# atmega328_core.net
KiCad netlist of a schematic drawn in EAGLE
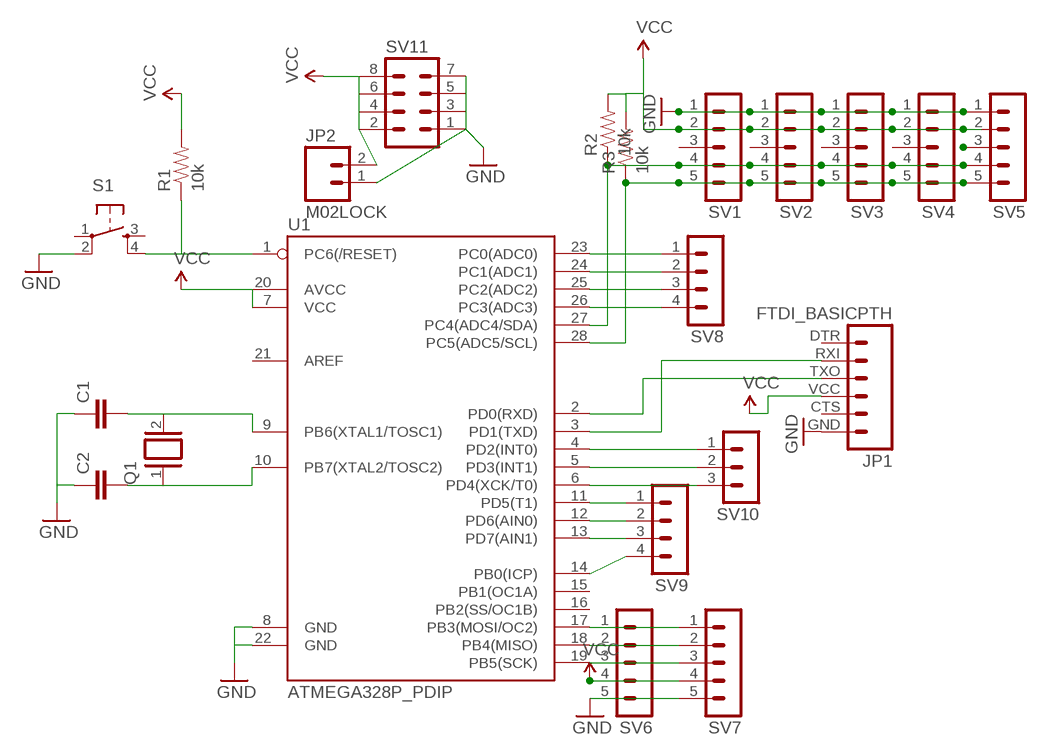
[diagram p0: schematic, sheet 1]

(export (version "E")
  (design (tool "Eeschema 10.0.6"))
  (components
    (comp (ref "C1")
      (value "CAPEZ")
      (footprint "eagle-import:CAP-PTH-SMALLEZ")
      (libsource (lib "eagle-import") (part "CAPEZ"))
    )
    (comp (ref "C2")
      (value "CAPEZ")
      (footprint "eagle-import:CAP-PTH-SMALLEZ")
      (libsource (lib "eagle-import") (part "CAPEZ"))
    )
    (comp (ref "JP1")
      (value "FTDI_BASICPTH")
      (footprint "eagle-import:FTDI_BASIC")
      (libsource (lib "eagle-import") (part "FTDI_BASICPTH"))
    )
    (comp (ref "JP2")
      (value "M02LOCK")
      (footprint "eagle-import:1X02_LOCK")
      (libsource (lib "eagle-import") (part "M02LOCK"))
    )
    (comp (ref "Q1")
      (value "XTAL/S")
      (footprint "eagle-import:QS")
      (libsource (lib "eagle-import") (part "XTAL/S"))
    )
    (comp (ref "R1")
      (value "10k")
      (footprint "eagle-import:AXIAL-0.3-KIT")
      (libsource (lib "eagle-import") (part "RESISTORKIT"))
    )
    (comp (ref "R2")
      (value "10k")
      (footprint "eagle-import:AXIAL-0.3-KIT")
      (libsource (lib "eagle-import") (part "RESISTORKIT"))
    )
    (comp (ref "R3")
      (value "10k")
      (footprint "eagle-import:AXIAL-0.3-KIT")
      (libsource (lib "eagle-import") (part "RESISTORKIT"))
    )
    (comp (ref "S1")
      (value "TAC_SWITCHPTH")
      (footprint "eagle-import:TACTILE-PTH")
      (libsource (lib "eagle-import") (part "TAC_SWITCHPTH"))
    )
    (comp (ref "SV1")
      (value "MA05-1")
      (footprint "eagle-import:MA05-1")
      (libsource (lib "eagle-import") (part "MA05-1"))
    )
    (comp (ref "SV2")
      (value "MA05-1")
      (footprint "eagle-import:MA05-1")
      (libsource (lib "eagle-import") (part "MA05-1"))
    )
    (comp (ref "SV3")
      (value "MA05-1")
      (footprint "eagle-import:MA05-1")
      (libsource (lib "eagle-import") (part "MA05-1"))
    )
    (comp (ref "SV4")
      (value "MA05-1")
      (footprint "eagle-import:MA05-1")
      (libsource (lib "eagle-import") (part "MA05-1"))
    )
    (comp (ref "SV5")
      (value "MA05-1")
      (footprint "eagle-import:MA05-1")
      (libsource (lib "eagle-import") (part "MA05-1"))
    )
    (comp (ref "SV6")
      (value "MA05-1")
      (footprint "eagle-import:MA05-1")
      (libsource (lib "eagle-import") (part "MA05-1"))
    )
    (comp (ref "SV7")
      (value "MA05-1")
      (footprint "eagle-import:MA05-1")
      (libsource (lib "eagle-import") (part "MA05-1"))
    )
    (comp (ref "SV8")
      (value "MA04-1")
      (footprint "eagle-import:MA04-1")
      (libsource (lib "eagle-import") (part "MA04-1"))
    )
    (comp (ref "SV9")
      (value "MA04-1")
      (footprint "eagle-import:MA04-1")
      (libsource (lib "eagle-import") (part "MA04-1"))
    )
    (comp (ref "SV10")
      (value "MA03-1")
      (footprint "eagle-import:MA03-1")
      (libsource (lib "eagle-import") (part "MA03-1"))
    )
    (comp (ref "SV11")
      (value "MA04-2")
      (footprint "eagle-import:MA04-2")
      (libsource (lib "eagle-import") (part "MA04-2"))
    )
    (comp (ref "U1")
      (value "ATMEGA328P_PDIP")
      (footprint "eagle-import:DIL28-3")
      (libsource (lib "eagle-import") (part "ATMEGA328P_PDIP"))
    )
  )
  (nets
    (net (code "1") (name "GND") (class "Default")
      (node (ref "C1") (pin "1") (pinfunction "1_1") (pintype "passive"))
      (node (ref "C2") (pin "1") (pinfunction "1_1") (pintype "passive"))
      (node (ref "JP1") (pin "GND") (pinfunction "6_GND") (pintype "passive"))
      (node (ref "JP2") (pin "1") (pinfunction "1_1") (pintype "passive"))
      (node (ref "S1") (pin "2") (pinfunction "2_2") (pintype "passive"))
      (node (ref "SV1") (pin "1") (pinfunction "1_1") (pintype "passive"))
      (node (ref "SV11") (pin "1") (pinfunction "1_1") (pintype "passive"))
      (node (ref "SV11") (pin "3") (pinfunction "3_3") (pintype "passive"))
      (node (ref "SV11") (pin "5") (pinfunction "5_5") (pintype "passive"))
      (node (ref "SV11") (pin "7") (pinfunction "7_7") (pintype "passive"))
      (node (ref "SV2") (pin "1") (pinfunction "1_1") (pintype "passive"))
      (node (ref "SV3") (pin "1") (pinfunction "1_1") (pintype "passive"))
      (node (ref "SV4") (pin "1") (pinfunction "1_1") (pintype "passive"))
      (node (ref "SV5") (pin "1") (pinfunction "1_1") (pintype "passive"))
      (node (ref "SV6") (pin "5") (pinfunction "5_5") (pintype "passive"))
      (node (ref "SV7") (pin "5") (pinfunction "5_5") (pintype "passive"))
      (node (ref "U1") (pin "22") (pinfunction "GND_22") (pintype "bidirectional"))
      (node (ref "U1") (pin "8") (pinfunction "GND_8") (pintype "bidirectional"))
    )
    (net (code "2") (name "Net-(JP1-2)") (class "Default")
      (node (ref "JP1") (pin "RXI") (pinfunction "2_RXI") (pintype "passive"))
      (node (ref "U1") (pin "3") (pinfunction "PD1(TXD)_3") (pintype "bidirectional"))
    )
    (net (code "3") (name "Net-(JP1-3)") (class "Default")
      (node (ref "JP1") (pin "TXO") (pinfunction "3_TXO") (pintype "passive"))
      (node (ref "U1") (pin "2") (pinfunction "PD0(RXD)_2") (pintype "bidirectional"))
    )
    (net (code "4") (name "Net-(R1-1)") (class "Default")
      (node (ref "R1") (pin "P$1") (pinfunction "1_P$1") (pintype "passive"))
      (node (ref "S1") (pin "4") (pinfunction "4_4") (pintype "passive"))
      (node (ref "U1") (pin "1") (pinfunction "PC6(/RESET)_1") (pintype "bidirectional"))
    )
    (net (code "5") (name "Net-(R2-1)") (class "Default")
      (node (ref "R2") (pin "P$1") (pinfunction "1_P$1") (pintype "passive"))
      (node (ref "SV1") (pin "4") (pinfunction "4_4") (pintype "passive"))
      (node (ref "SV2") (pin "4") (pinfunction "4_4") (pintype "passive"))
      (node (ref "SV3") (pin "4") (pinfunction "4_4") (pintype "passive"))
      (node (ref "SV4") (pin "4") (pinfunction "4_4") (pintype "passive"))
      (node (ref "SV5") (pin "4") (pinfunction "4_4") (pintype "passive"))
      (node (ref "U1") (pin "27") (pinfunction "PC4(ADC4/SDA)_27") (pintype "bidirectional"))
    )
    (net (code "6") (name "Net-(R3-1)") (class "Default")
      (node (ref "R3") (pin "P$1") (pinfunction "1_P$1") (pintype "passive"))
      (node (ref "SV1") (pin "5") (pinfunction "5_5") (pintype "passive"))
      (node (ref "SV2") (pin "5") (pinfunction "5_5") (pintype "passive"))
      (node (ref "SV3") (pin "5") (pinfunction "5_5") (pintype "passive"))
      (node (ref "SV4") (pin "5") (pinfunction "5_5") (pintype "passive"))
      (node (ref "SV5") (pin "5") (pinfunction "5_5") (pintype "passive"))
      (node (ref "U1") (pin "28") (pinfunction "PC5(ADC5/SCL)_28") (pintype "bidirectional"))
    )
    (net (code "7") (name "Net-(U1-PB0(ICP))") (class "Default")
      (node (ref "SV9") (pin "4") (pinfunction "4_4") (pintype "passive"))
      (node (ref "U1") (pin "14") (pinfunction "PB0(ICP)_14") (pintype "bidirectional"))
    )
    (net (code "8") (name "Net-(U1-PB3(MOSI{slash}OC2))") (class "Default")
      (node (ref "SV6") (pin "1") (pinfunction "1_1") (pintype "passive"))
      (node (ref "SV7") (pin "1") (pinfunction "1_1") (pintype "passive"))
      (node (ref "U1") (pin "17") (pinfunction "PB3(MOSI/OC2)_17") (pintype "bidirectional"))
    )
    (net (code "9") (name "Net-(U1-PB4(MISO))") (class "Default")
      (node (ref "SV6") (pin "2") (pinfunction "2_2") (pintype "passive"))
      (node (ref "SV7") (pin "2") (pinfunction "2_2") (pintype "passive"))
      (node (ref "U1") (pin "18") (pinfunction "PB4(MISO)_18") (pintype "bidirectional"))
    )
    (net (code "10") (name "Net-(U1-PB5(SCK))") (class "Default")
      (node (ref "SV6") (pin "3") (pinfunction "3_3") (pintype "passive"))
      (node (ref "SV7") (pin "3") (pinfunction "3_3") (pintype "passive"))
      (node (ref "U1") (pin "19") (pinfunction "PB5(SCK)_19") (pintype "bidirectional"))
    )
    (net (code "11") (name "Net-(U1-PB6(XTAL1{slash}TOSC1))") (class "Default")
      (node (ref "C1") (pin "2") (pinfunction "2_2") (pintype "passive"))
      (node (ref "Q1") (pin "2") (pinfunction "2_2") (pintype "passive"))
      (node (ref "U1") (pin "9") (pinfunction "PB6(XTAL1/TOSC1)_9") (pintype "bidirectional"))
    )
    (net (code "12") (name "Net-(U1-PB7(XTAL2{slash}TOSC2))") (class "Default")
      (node (ref "C2") (pin "2") (pinfunction "2_2") (pintype "passive"))
      (node (ref "Q1") (pin "1") (pinfunction "1_1") (pintype "passive"))
      (node (ref "U1") (pin "10") (pinfunction "PB7(XTAL2/TOSC2)_10") (pintype "bidirectional"))
    )
    (net (code "13") (name "Net-(U1-PC0(ADC0))") (class "Default")
      (node (ref "SV8") (pin "1") (pinfunction "1_1") (pintype "passive"))
      (node (ref "U1") (pin "23") (pinfunction "PC0(ADC0)_23") (pintype "bidirectional"))
    )
    (net (code "14") (name "Net-(U1-PC1(ADC1))") (class "Default")
      (node (ref "SV8") (pin "2") (pinfunction "2_2") (pintype "passive"))
      (node (ref "U1") (pin "24") (pinfunction "PC1(ADC1)_24") (pintype "bidirectional"))
    )
    (net (code "15") (name "Net-(U1-PC2(ADC2))") (class "Default")
      (node (ref "SV8") (pin "3") (pinfunction "3_3") (pintype "passive"))
      (node (ref "U1") (pin "25") (pinfunction "PC2(ADC2)_25") (pintype "bidirectional"))
    )
    (net (code "16") (name "Net-(U1-PC3(ADC3))") (class "Default")
      (node (ref "SV8") (pin "4") (pinfunction "4_4") (pintype "passive"))
      (node (ref "U1") (pin "26") (pinfunction "PC3(ADC3)_26") (pintype "bidirectional"))
    )
    (net (code "17") (name "Net-(U1-PD2(INT0))") (class "Default")
      (node (ref "SV10") (pin "1") (pinfunction "1_1") (pintype "passive"))
      (node (ref "U1") (pin "4") (pinfunction "PD2(INT0)_4") (pintype "bidirectional"))
    )
    (net (code "18") (name "Net-(U1-PD3(INT1))") (class "Default")
      (node (ref "SV10") (pin "2") (pinfunction "2_2") (pintype "passive"))
      (node (ref "U1") (pin "5") (pinfunction "PD3(INT1)_5") (pintype "bidirectional"))
    )
    (net (code "19") (name "Net-(U1-PD4(XCK{slash}T0))") (class "Default")
      (node (ref "SV10") (pin "3") (pinfunction "3_3") (pintype "passive"))
      (node (ref "U1") (pin "6") (pinfunction "PD4(XCK/T0)_6") (pintype "bidirectional"))
    )
    (net (code "20") (name "Net-(U1-PD5(T1))") (class "Default")
      (node (ref "SV9") (pin "1") (pinfunction "1_1") (pintype "passive"))
      (node (ref "U1") (pin "11") (pinfunction "PD5(T1)_11") (pintype "bidirectional"))
    )
    (net (code "21") (name "Net-(U1-PD6(AIN0))") (class "Default")
      (node (ref "SV9") (pin "2") (pinfunction "2_2") (pintype "passive"))
      (node (ref "U1") (pin "12") (pinfunction "PD6(AIN0)_12") (pintype "bidirectional"))
    )
    (net (code "22") (name "Net-(U1-PD7(AIN1))") (class "Default")
      (node (ref "SV9") (pin "3") (pinfunction "3_3") (pintype "passive"))
      (node (ref "U1") (pin "13") (pinfunction "PD7(AIN1)_13") (pintype "bidirectional"))
    )
    (net (code "23") (name "VCC") (class "Default")
      (node (ref "JP1") (pin "VCC") (pinfunction "4_VCC") (pintype "passive"))
      (node (ref "JP2") (pin "2") (pinfunction "2_2") (pintype "passive"))
      (node (ref "R1") (pin "P$2") (pinfunction "2_P$2") (pintype "passive"))
      (node (ref "R2") (pin "P$2") (pinfunction "2_P$2") (pintype "passive"))
      (node (ref "R3") (pin "P$2") (pinfunction "2_P$2") (pintype "passive"))
      (node (ref "SV1") (pin "2") (pinfunction "2_2") (pintype "passive"))
      (node (ref "SV11") (pin "2") (pinfunction "2_2") (pintype "passive"))
      (node (ref "SV11") (pin "4") (pinfunction "4_4") (pintype "passive"))
      (node (ref "SV11") (pin "6") (pinfunction "6_6") (pintype "passive"))
      (node (ref "SV11") (pin "8") (pinfunction "8_8") (pintype "passive"))
      (node (ref "SV2") (pin "2") (pinfunction "2_2") (pintype "passive"))
      (node (ref "SV3") (pin "2") (pinfunction "2_2") (pintype "passive"))
      (node (ref "SV4") (pin "2") (pinfunction "2_2") (pintype "passive"))
      (node (ref "SV5") (pin "2") (pinfunction "2_2") (pintype "passive"))
      (node (ref "SV6") (pin "4") (pinfunction "4_4") (pintype "passive"))
      (node (ref "SV7") (pin "4") (pinfunction "4_4") (pintype "passive"))
      (node (ref "U1") (pin "20") (pinfunction "AVCC_20") (pintype "bidirectional"))
      (node (ref "U1") (pin "7") (pinfunction "VCC_7") (pintype "bidirectional"))
    )
    (net (code "24") (name "unconnected-(JP1-1-PadDTR)") (class "Default")
      (node (ref "JP1") (pin "DTR") (pinfunction "1_DTR") (pintype "passive"))
    )
    (net (code "25") (name "unconnected-(JP1-5-PadCTS)") (class "Default")
      (node (ref "JP1") (pin "CTS") (pinfunction "5_CTS") (pintype "passive"))
    )
    (net (code "26") (name "unconnected-(S1-Pad1)") (class "Default")
      (node (ref "S1") (pin "1") (pinfunction "1_1") (pintype "passive"))
    )
    (net (code "27") (name "unconnected-(S1-Pad3)") (class "Default")
      (node (ref "S1") (pin "3") (pinfunction "3_3") (pintype "passive"))
    )
    (net (code "28") (name "unconnected-(SV1-Pad3)") (class "Default")
      (node (ref "SV1") (pin "3") (pinfunction "3_3") (pintype "passive"))
    )
    (net (code "29") (name "unconnected-(SV2-Pad3)") (class "Default")
      (node (ref "SV2") (pin "3") (pinfunction "3_3") (pintype "passive"))
    )
    (net (code "30") (name "unconnected-(SV3-Pad3)") (class "Default")
      (node (ref "SV3") (pin "3") (pinfunction "3_3") (pintype "passive"))
    )
    (net (code "31") (name "unconnected-(SV4-Pad3)") (class "Default")
      (node (ref "SV4") (pin "3") (pinfunction "3_3") (pintype "passive"))
    )
    (net (code "32") (name "unconnected-(SV5-Pad3)") (class "Default")
      (node (ref "SV5") (pin "3") (pinfunction "3_3") (pintype "passive"))
    )
    (net (code "33") (name "unconnected-(U1-AREF-Pad21)") (class "Default")
      (node (ref "U1") (pin "21") (pinfunction "AREF_21") (pintype "bidirectional"))
    )
    (net (code "34") (name "unconnected-(U1-PB1(OC1A)-Pad15)") (class "Default")
      (node (ref "U1") (pin "15") (pinfunction "PB1(OC1A)_15") (pintype "bidirectional"))
    )
    (net (code "35") (name "unconnected-(U1-PB2(SS{slash}OC1B)-Pad16)") (class "Default")
      (node (ref "U1") (pin "16") (pinfunction "PB2(SS/OC1B)_16") (pintype "bidirectional"))
    )
  )
)
